# 04_-_7_SEGMENT_DISPS.net
KiCad netlist of a schematic drawn in Altium Designer
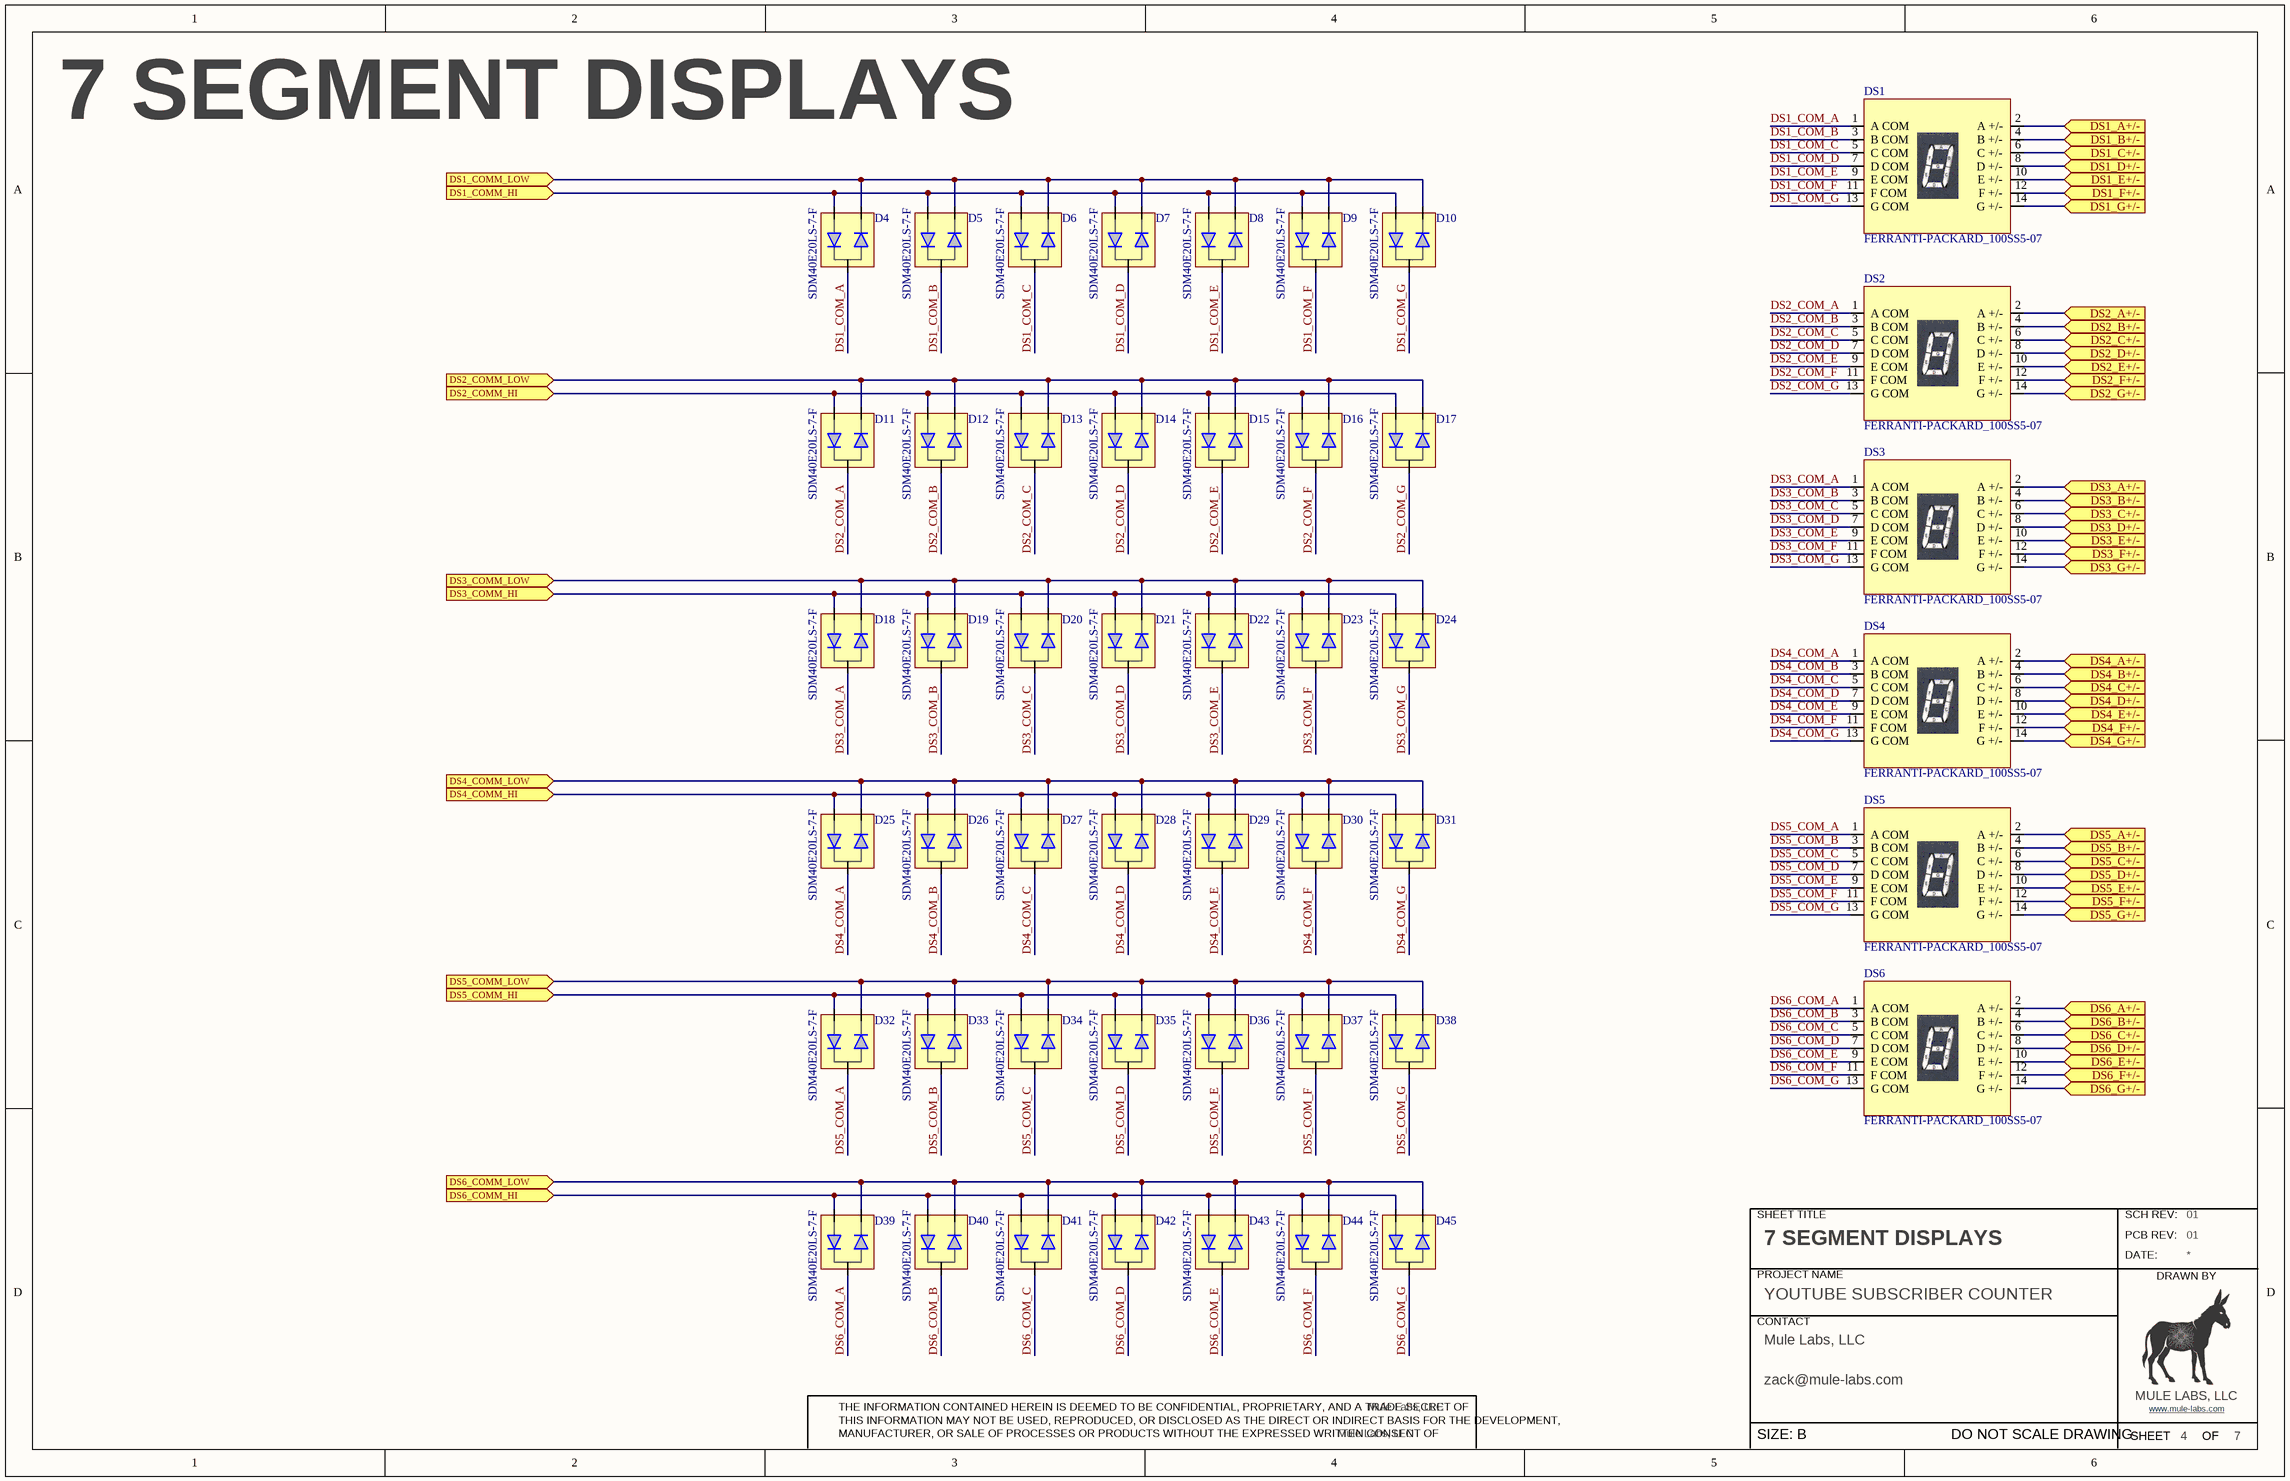
[diagram p0: [04] - 7 SEGMENT DISPS.SchDoc]

(export (version "E")
  (design (tool "Eeschema 10.0.6"))
  (components
    (comp (ref "D4")
      (value "SDM40E20LS-7-F")
      (footprint "SOT23-3P95_240X110L40X44")
      (description "DIODE ARRAY SCHOTTKY 20V SOT23-3")
      (fields (field (name "MANUFACTURER") "Diodes"))
      (libsource (lib "Diodes") (part "SDM40E20LS-7-F"))
    )
    (comp (ref "D5")
      (value "SDM40E20LS-7-F")
      (footprint "SOT23-3P95_240X110L40X44")
      (description "DIODE ARRAY SCHOTTKY 20V SOT23-3")
      (fields (field (name "MANUFACTURER") "Diodes"))
      (libsource (lib "Diodes") (part "SDM40E20LS-7-F"))
    )
    (comp (ref "D6")
      (value "SDM40E20LS-7-F")
      (footprint "SOT23-3P95_240X110L40X44")
      (description "DIODE ARRAY SCHOTTKY 20V SOT23-3")
      (fields (field (name "MANUFACTURER") "Diodes"))
      (libsource (lib "Diodes") (part "SDM40E20LS-7-F"))
    )
    (comp (ref "D7")
      (value "SDM40E20LS-7-F")
      (footprint "SOT23-3P95_240X110L40X44")
      (description "DIODE ARRAY SCHOTTKY 20V SOT23-3")
      (fields (field (name "MANUFACTURER") "Diodes"))
      (libsource (lib "Diodes") (part "SDM40E20LS-7-F"))
    )
    (comp (ref "D8")
      (value "SDM40E20LS-7-F")
      (footprint "SOT23-3P95_240X110L40X44")
      (description "DIODE ARRAY SCHOTTKY 20V SOT23-3")
      (fields (field (name "MANUFACTURER") "Diodes"))
      (libsource (lib "Diodes") (part "SDM40E20LS-7-F"))
    )
    (comp (ref "D9")
      (value "SDM40E20LS-7-F")
      (footprint "SOT23-3P95_240X110L40X44")
      (description "DIODE ARRAY SCHOTTKY 20V SOT23-3")
      (fields (field (name "MANUFACTURER") "Diodes"))
      (libsource (lib "Diodes") (part "SDM40E20LS-7-F"))
    )
    (comp (ref "D10")
      (value "SDM40E20LS-7-F")
      (footprint "SOT23-3P95_240X110L40X44")
      (description "DIODE ARRAY SCHOTTKY 20V SOT23-3")
      (fields (field (name "MANUFACTURER") "Diodes"))
      (libsource (lib "Diodes") (part "SDM40E20LS-7-F"))
    )
    (comp (ref "D11")
      (value "SDM40E20LS-7-F")
      (footprint "SOT23-3P95_240X110L40X44")
      (description "DIODE ARRAY SCHOTTKY 20V SOT23-3")
      (fields (field (name "MANUFACTURER") "Diodes"))
      (libsource (lib "Diodes") (part "SDM40E20LS-7-F"))
    )
    (comp (ref "D12")
      (value "SDM40E20LS-7-F")
      (footprint "SOT23-3P95_240X110L40X44")
      (description "DIODE ARRAY SCHOTTKY 20V SOT23-3")
      (fields (field (name "MANUFACTURER") "Diodes"))
      (libsource (lib "Diodes") (part "SDM40E20LS-7-F"))
    )
    (comp (ref "D13")
      (value "SDM40E20LS-7-F")
      (footprint "SOT23-3P95_240X110L40X44")
      (description "DIODE ARRAY SCHOTTKY 20V SOT23-3")
      (fields (field (name "MANUFACTURER") "Diodes"))
      (libsource (lib "Diodes") (part "SDM40E20LS-7-F"))
    )
    (comp (ref "D14")
      (value "SDM40E20LS-7-F")
      (footprint "SOT23-3P95_240X110L40X44")
      (description "DIODE ARRAY SCHOTTKY 20V SOT23-3")
      (fields (field (name "MANUFACTURER") "Diodes"))
      (libsource (lib "Diodes") (part "SDM40E20LS-7-F"))
    )
    (comp (ref "D15")
      (value "SDM40E20LS-7-F")
      (footprint "SOT23-3P95_240X110L40X44")
      (description "DIODE ARRAY SCHOTTKY 20V SOT23-3")
      (fields (field (name "MANUFACTURER") "Diodes"))
      (libsource (lib "Diodes") (part "SDM40E20LS-7-F"))
    )
    (comp (ref "D16")
      (value "SDM40E20LS-7-F")
      (footprint "SOT23-3P95_240X110L40X44")
      (description "DIODE ARRAY SCHOTTKY 20V SOT23-3")
      (fields (field (name "MANUFACTURER") "Diodes"))
      (libsource (lib "Diodes") (part "SDM40E20LS-7-F"))
    )
    (comp (ref "D17")
      (value "SDM40E20LS-7-F")
      (footprint "SOT23-3P95_240X110L40X44")
      (description "DIODE ARRAY SCHOTTKY 20V SOT23-3")
      (fields (field (name "MANUFACTURER") "Diodes"))
      (libsource (lib "Diodes") (part "SDM40E20LS-7-F"))
    )
    (comp (ref "D18")
      (value "SDM40E20LS-7-F")
      (footprint "SOT23-3P95_240X110L40X44")
      (description "DIODE ARRAY SCHOTTKY 20V SOT23-3")
      (fields (field (name "MANUFACTURER") "Diodes"))
      (libsource (lib "Diodes") (part "SDM40E20LS-7-F"))
    )
    (comp (ref "D19")
      (value "SDM40E20LS-7-F")
      (footprint "SOT23-3P95_240X110L40X44")
      (description "DIODE ARRAY SCHOTTKY 20V SOT23-3")
      (fields (field (name "MANUFACTURER") "Diodes"))
      (libsource (lib "Diodes") (part "SDM40E20LS-7-F"))
    )
    (comp (ref "D20")
      (value "SDM40E20LS-7-F")
      (footprint "SOT23-3P95_240X110L40X44")
      (description "DIODE ARRAY SCHOTTKY 20V SOT23-3")
      (fields (field (name "MANUFACTURER") "Diodes"))
      (libsource (lib "Diodes") (part "SDM40E20LS-7-F"))
    )
    (comp (ref "D21")
      (value "SDM40E20LS-7-F")
      (footprint "SOT23-3P95_240X110L40X44")
      (description "DIODE ARRAY SCHOTTKY 20V SOT23-3")
      (fields (field (name "MANUFACTURER") "Diodes"))
      (libsource (lib "Diodes") (part "SDM40E20LS-7-F"))
    )
    (comp (ref "D22")
      (value "SDM40E20LS-7-F")
      (footprint "SOT23-3P95_240X110L40X44")
      (description "DIODE ARRAY SCHOTTKY 20V SOT23-3")
      (fields (field (name "MANUFACTURER") "Diodes"))
      (libsource (lib "Diodes") (part "SDM40E20LS-7-F"))
    )
    (comp (ref "D23")
      (value "SDM40E20LS-7-F")
      (footprint "SOT23-3P95_240X110L40X44")
      (description "DIODE ARRAY SCHOTTKY 20V SOT23-3")
      (fields (field (name "MANUFACTURER") "Diodes"))
      (libsource (lib "Diodes") (part "SDM40E20LS-7-F"))
    )
    (comp (ref "D24")
      (value "SDM40E20LS-7-F")
      (footprint "SOT23-3P95_240X110L40X44")
      (description "DIODE ARRAY SCHOTTKY 20V SOT23-3")
      (fields (field (name "MANUFACTURER") "Diodes"))
      (libsource (lib "Diodes") (part "SDM40E20LS-7-F"))
    )
    (comp (ref "D25")
      (value "SDM40E20LS-7-F")
      (footprint "SOT23-3P95_240X110L40X44")
      (description "DIODE ARRAY SCHOTTKY 20V SOT23-3")
      (fields (field (name "MANUFACTURER") "Diodes"))
      (libsource (lib "Diodes") (part "SDM40E20LS-7-F"))
    )
    (comp (ref "D26")
      (value "SDM40E20LS-7-F")
      (footprint "SOT23-3P95_240X110L40X44")
      (description "DIODE ARRAY SCHOTTKY 20V SOT23-3")
      (fields (field (name "MANUFACTURER") "Diodes"))
      (libsource (lib "Diodes") (part "SDM40E20LS-7-F"))
    )
    (comp (ref "D27")
      (value "SDM40E20LS-7-F")
      (footprint "SOT23-3P95_240X110L40X44")
      (description "DIODE ARRAY SCHOTTKY 20V SOT23-3")
      (fields (field (name "MANUFACTURER") "Diodes"))
      (libsource (lib "Diodes") (part "SDM40E20LS-7-F"))
    )
    (comp (ref "D28")
      (value "SDM40E20LS-7-F")
      (footprint "SOT23-3P95_240X110L40X44")
      (description "DIODE ARRAY SCHOTTKY 20V SOT23-3")
      (fields (field (name "MANUFACTURER") "Diodes"))
      (libsource (lib "Diodes") (part "SDM40E20LS-7-F"))
    )
    (comp (ref "D29")
      (value "SDM40E20LS-7-F")
      (footprint "SOT23-3P95_240X110L40X44")
      (description "DIODE ARRAY SCHOTTKY 20V SOT23-3")
      (fields (field (name "MANUFACTURER") "Diodes"))
      (libsource (lib "Diodes") (part "SDM40E20LS-7-F"))
    )
    (comp (ref "D30")
      (value "SDM40E20LS-7-F")
      (footprint "SOT23-3P95_240X110L40X44")
      (description "DIODE ARRAY SCHOTTKY 20V SOT23-3")
      (fields (field (name "MANUFACTURER") "Diodes"))
      (libsource (lib "Diodes") (part "SDM40E20LS-7-F"))
    )
    (comp (ref "D31")
      (value "SDM40E20LS-7-F")
      (footprint "SOT23-3P95_240X110L40X44")
      (description "DIODE ARRAY SCHOTTKY 20V SOT23-3")
      (fields (field (name "MANUFACTURER") "Diodes"))
      (libsource (lib "Diodes") (part "SDM40E20LS-7-F"))
    )
    (comp (ref "D32")
      (value "SDM40E20LS-7-F")
      (footprint "SOT23-3P95_240X110L40X44")
      (description "DIODE ARRAY SCHOTTKY 20V SOT23-3")
      (fields (field (name "MANUFACTURER") "Diodes"))
      (libsource (lib "Diodes") (part "SDM40E20LS-7-F"))
    )
    (comp (ref "D33")
      (value "SDM40E20LS-7-F")
      (footprint "SOT23-3P95_240X110L40X44")
      (description "DIODE ARRAY SCHOTTKY 20V SOT23-3")
      (fields (field (name "MANUFACTURER") "Diodes"))
      (libsource (lib "Diodes") (part "SDM40E20LS-7-F"))
    )
    (comp (ref "D34")
      (value "SDM40E20LS-7-F")
      (footprint "SOT23-3P95_240X110L40X44")
      (description "DIODE ARRAY SCHOTTKY 20V SOT23-3")
      (fields (field (name "MANUFACTURER") "Diodes"))
      (libsource (lib "Diodes") (part "SDM40E20LS-7-F"))
    )
    (comp (ref "D35")
      (value "SDM40E20LS-7-F")
      (footprint "SOT23-3P95_240X110L40X44")
      (description "DIODE ARRAY SCHOTTKY 20V SOT23-3")
      (fields (field (name "MANUFACTURER") "Diodes"))
      (libsource (lib "Diodes") (part "SDM40E20LS-7-F"))
    )
    (comp (ref "D36")
      (value "SDM40E20LS-7-F")
      (footprint "SOT23-3P95_240X110L40X44")
      (description "DIODE ARRAY SCHOTTKY 20V SOT23-3")
      (fields (field (name "MANUFACTURER") "Diodes"))
      (libsource (lib "Diodes") (part "SDM40E20LS-7-F"))
    )
    (comp (ref "D37")
      (value "SDM40E20LS-7-F")
      (footprint "SOT23-3P95_240X110L40X44")
      (description "DIODE ARRAY SCHOTTKY 20V SOT23-3")
      (fields (field (name "MANUFACTURER") "Diodes"))
      (libsource (lib "Diodes") (part "SDM40E20LS-7-F"))
    )
    (comp (ref "D38")
      (value "SDM40E20LS-7-F")
      (footprint "SOT23-3P95_240X110L40X44")
      (description "DIODE ARRAY SCHOTTKY 20V SOT23-3")
      (fields (field (name "MANUFACTURER") "Diodes"))
      (libsource (lib "Diodes") (part "SDM40E20LS-7-F"))
    )
    (comp (ref "D39")
      (value "SDM40E20LS-7-F")
      (footprint "SOT23-3P95_240X110L40X44")
      (description "DIODE ARRAY SCHOTTKY 20V SOT23-3")
      (fields (field (name "MANUFACTURER") "Diodes"))
      (libsource (lib "Diodes") (part "SDM40E20LS-7-F"))
    )
    (comp (ref "D40")
      (value "SDM40E20LS-7-F")
      (footprint "SOT23-3P95_240X110L40X44")
      (description "DIODE ARRAY SCHOTTKY 20V SOT23-3")
      (fields (field (name "MANUFACTURER") "Diodes"))
      (libsource (lib "Diodes") (part "SDM40E20LS-7-F"))
    )
    (comp (ref "D41")
      (value "SDM40E20LS-7-F")
      (footprint "SOT23-3P95_240X110L40X44")
      (description "DIODE ARRAY SCHOTTKY 20V SOT23-3")
      (fields (field (name "MANUFACTURER") "Diodes"))
      (libsource (lib "Diodes") (part "SDM40E20LS-7-F"))
    )
    (comp (ref "D42")
      (value "SDM40E20LS-7-F")
      (footprint "SOT23-3P95_240X110L40X44")
      (description "DIODE ARRAY SCHOTTKY 20V SOT23-3")
      (fields (field (name "MANUFACTURER") "Diodes"))
      (libsource (lib "Diodes") (part "SDM40E20LS-7-F"))
    )
    (comp (ref "D43")
      (value "SDM40E20LS-7-F")
      (footprint "SOT23-3P95_240X110L40X44")
      (description "DIODE ARRAY SCHOTTKY 20V SOT23-3")
      (fields (field (name "MANUFACTURER") "Diodes"))
      (libsource (lib "Diodes") (part "SDM40E20LS-7-F"))
    )
    (comp (ref "D44")
      (value "SDM40E20LS-7-F")
      (footprint "SOT23-3P95_240X110L40X44")
      (description "DIODE ARRAY SCHOTTKY 20V SOT23-3")
      (fields (field (name "MANUFACTURER") "Diodes"))
      (libsource (lib "Diodes") (part "SDM40E20LS-7-F"))
    )
    (comp (ref "D45")
      (value "SDM40E20LS-7-F")
      (footprint "SOT23-3P95_240X110L40X44")
      (description "DIODE ARRAY SCHOTTKY 20V SOT23-3")
      (fields (field (name "MANUFACTURER") "Diodes"))
      (libsource (lib "Diodes") (part "SDM40E20LS-7-F"))
    )
    (comp (ref "DS1")
      (value "FERRANTI-PACKARD_100SS5-07")
      (footprint "FERRANTI_EM_7SEG")
      (description "ELECTROMECHANICAL 7-SEGMENT DISPLAY")
      (libsource (lib "Displays") (part "FERRANTI_PACKARD_7SEG"))
    )
    (comp (ref "DS2")
      (value "FERRANTI-PACKARD_100SS5-07")
      (footprint "FERRANTI_EM_7SEG")
      (description "ELECTROMECHANICAL 7-SEGMENT DISPLAY")
      (libsource (lib "Displays") (part "FERRANTI_PACKARD_7SEG"))
    )
    (comp (ref "DS3")
      (value "FERRANTI-PACKARD_100SS5-07")
      (footprint "FERRANTI_EM_7SEG")
      (description "ELECTROMECHANICAL 7-SEGMENT DISPLAY")
      (libsource (lib "Displays") (part "FERRANTI_PACKARD_7SEG"))
    )
    (comp (ref "DS4")
      (value "FERRANTI-PACKARD_100SS5-07")
      (footprint "FERRANTI_EM_7SEG")
      (description "ELECTROMECHANICAL 7-SEGMENT DISPLAY")
      (libsource (lib "Displays") (part "FERRANTI_PACKARD_7SEG"))
    )
    (comp (ref "DS5")
      (value "FERRANTI-PACKARD_100SS5-07")
      (footprint "FERRANTI_EM_7SEG")
      (description "ELECTROMECHANICAL 7-SEGMENT DISPLAY")
      (libsource (lib "Displays") (part "FERRANTI_PACKARD_7SEG"))
    )
    (comp (ref "DS6")
      (value "FERRANTI-PACKARD_100SS5-07")
      (footprint "FERRANTI_EM_7SEG")
      (description "ELECTROMECHANICAL 7-SEGMENT DISPLAY")
      (libsource (lib "Displays") (part "FERRANTI_PACKARD_7SEG"))
    )
  )
  (nets
    (net (code "1") (name "/DS1_A+{slash}-") (class "Default")
      (node (ref "DS1") (pin "2") (pinfunction "A_+/-_2") (pintype "passive"))
    )
    (net (code "2") (name "/DS1_B+{slash}-") (class "Default")
      (node (ref "DS1") (pin "4") (pinfunction "B_+/-_4") (pintype "passive"))
    )
    (net (code "3") (name "/DS1_C+{slash}-") (class "Default")
      (node (ref "DS1") (pin "6") (pinfunction "C_+/-_6") (pintype "passive"))
    )
    (net (code "4") (name "/DS1_COMM_HI") (class "Default")
      (node (ref "D10") (pin "1") (pintype "passive"))
      (node (ref "D4") (pin "1") (pintype "passive"))
      (node (ref "D5") (pin "1") (pintype "passive"))
      (node (ref "D6") (pin "1") (pintype "passive"))
      (node (ref "D7") (pin "1") (pintype "passive"))
      (node (ref "D8") (pin "1") (pintype "passive"))
      (node (ref "D9") (pin "1") (pintype "passive"))
    )
    (net (code "5") (name "/DS1_COMM_LOW") (class "Default")
      (node (ref "D10") (pin "2") (pintype "passive"))
      (node (ref "D4") (pin "2") (pintype "passive"))
      (node (ref "D5") (pin "2") (pintype "passive"))
      (node (ref "D6") (pin "2") (pintype "passive"))
      (node (ref "D7") (pin "2") (pintype "passive"))
      (node (ref "D8") (pin "2") (pintype "passive"))
      (node (ref "D9") (pin "2") (pintype "passive"))
    )
    (net (code "6") (name "/DS1_COM_A") (class "Default")
      (node (ref "D4") (pin "3") (pintype "passive"))
      (node (ref "DS1") (pin "1") (pinfunction "A_COM_1") (pintype "passive"))
    )
    (net (code "7") (name "/DS1_COM_B") (class "Default")
      (node (ref "D5") (pin "3") (pintype "passive"))
      (node (ref "DS1") (pin "3") (pinfunction "B_COM_3") (pintype "passive"))
    )
    (net (code "8") (name "/DS1_COM_C") (class "Default")
      (node (ref "D6") (pin "3") (pintype "passive"))
      (node (ref "DS1") (pin "5") (pinfunction "C_COM_5") (pintype "passive"))
    )
    (net (code "9") (name "/DS1_COM_D") (class "Default")
      (node (ref "D7") (pin "3") (pintype "passive"))
      (node (ref "DS1") (pin "7") (pinfunction "D_COM_7") (pintype "passive"))
    )
    (net (code "10") (name "/DS1_COM_E") (class "Default")
      (node (ref "D8") (pin "3") (pintype "passive"))
      (node (ref "DS1") (pin "9") (pinfunction "E_COM_9") (pintype "passive"))
    )
    (net (code "11") (name "/DS1_COM_F") (class "Default")
      (node (ref "D9") (pin "3") (pintype "passive"))
      (node (ref "DS1") (pin "11") (pinfunction "F_COM_11") (pintype "passive"))
    )
    (net (code "12") (name "/DS1_COM_G") (class "Default")
      (node (ref "D10") (pin "3") (pintype "passive"))
      (node (ref "DS1") (pin "13") (pinfunction "G_COM_13") (pintype "passive"))
    )
    (net (code "13") (name "/DS1_D+{slash}-") (class "Default")
      (node (ref "DS1") (pin "8") (pinfunction "D_+/-_8") (pintype "passive"))
    )
    (net (code "14") (name "/DS1_E+{slash}-") (class "Default")
      (node (ref "DS1") (pin "10") (pinfunction "E_+/-_10") (pintype "passive"))
    )
    (net (code "15") (name "/DS1_F+{slash}-") (class "Default")
      (node (ref "DS1") (pin "12") (pinfunction "F_+/-_12") (pintype "passive"))
    )
    (net (code "16") (name "/DS1_G+{slash}-") (class "Default")
      (node (ref "DS1") (pin "14") (pinfunction "G_+/-_14") (pintype "passive"))
    )
    (net (code "17") (name "/DS2_A+{slash}-") (class "Default")
      (node (ref "DS2") (pin "2") (pinfunction "A_+/-_2") (pintype "passive"))
    )
    (net (code "18") (name "/DS2_B+{slash}-") (class "Default")
      (node (ref "DS2") (pin "4") (pinfunction "B_+/-_4") (pintype "passive"))
    )
    (net (code "19") (name "/DS2_C+{slash}-") (class "Default")
      (node (ref "DS2") (pin "6") (pinfunction "C_+/-_6") (pintype "passive"))
    )
    (net (code "20") (name "/DS2_COMM_HI") (class "Default")
      (node (ref "D11") (pin "1") (pintype "passive"))
      (node (ref "D12") (pin "1") (pintype "passive"))
      (node (ref "D13") (pin "1") (pintype "passive"))
      (node (ref "D14") (pin "1") (pintype "passive"))
      (node (ref "D15") (pin "1") (pintype "passive"))
      (node (ref "D16") (pin "1") (pintype "passive"))
      (node (ref "D17") (pin "1") (pintype "passive"))
    )
    (net (code "21") (name "/DS2_COMM_LOW") (class "Default")
      (node (ref "D11") (pin "2") (pintype "passive"))
      (node (ref "D12") (pin "2") (pintype "passive"))
      (node (ref "D13") (pin "2") (pintype "passive"))
      (node (ref "D14") (pin "2") (pintype "passive"))
      (node (ref "D15") (pin "2") (pintype "passive"))
      (node (ref "D16") (pin "2") (pintype "passive"))
      (node (ref "D17") (pin "2") (pintype "passive"))
    )
    (net (code "22") (name "/DS2_COM_A") (class "Default")
      (node (ref "D11") (pin "3") (pintype "passive"))
      (node (ref "DS2") (pin "1") (pinfunction "A_COM_1") (pintype "passive"))
    )
    (net (code "23") (name "/DS2_COM_B") (class "Default")
      (node (ref "D12") (pin "3") (pintype "passive"))
      (node (ref "DS2") (pin "3") (pinfunction "B_COM_3") (pintype "passive"))
    )
    (net (code "24") (name "/DS2_COM_C") (class "Default")
      (node (ref "D13") (pin "3") (pintype "passive"))
      (node (ref "DS2") (pin "5") (pinfunction "C_COM_5") (pintype "passive"))
    )
    (net (code "25") (name "/DS2_COM_D") (class "Default")
      (node (ref "D14") (pin "3") (pintype "passive"))
      (node (ref "DS2") (pin "7") (pinfunction "D_COM_7") (pintype "passive"))
    )
    (net (code "26") (name "/DS2_COM_E") (class "Default")
      (node (ref "D15") (pin "3") (pintype "passive"))
      (node (ref "DS2") (pin "9") (pinfunction "E_COM_9") (pintype "passive"))
    )
    (net (code "27") (name "/DS2_COM_F") (class "Default")
      (node (ref "D16") (pin "3") (pintype "passive"))
      (node (ref "DS2") (pin "11") (pinfunction "F_COM_11") (pintype "passive"))
    )
    (net (code "28") (name "/DS2_COM_G") (class "Default")
      (node (ref "D17") (pin "3") (pintype "passive"))
      (node (ref "DS2") (pin "13") (pinfunction "G_COM_13") (pintype "passive"))
    )
    (net (code "29") (name "/DS2_D+{slash}-") (class "Default")
      (node (ref "DS2") (pin "8") (pinfunction "D_+/-_8") (pintype "passive"))
    )
    (net (code "30") (name "/DS2_E+{slash}-") (class "Default")
      (node (ref "DS2") (pin "10") (pinfunction "E_+/-_10") (pintype "passive"))
    )
    (net (code "31") (name "/DS2_F+{slash}-") (class "Default")
      (node (ref "DS2") (pin "12") (pinfunction "F_+/-_12") (pintype "passive"))
    )
    (net (code "32") (name "/DS2_G+{slash}-") (class "Default")
      (node (ref "DS2") (pin "14") (pinfunction "G_+/-_14") (pintype "passive"))
    )
    (net (code "33") (name "/DS3_A+{slash}-") (class "Default")
      (node (ref "DS3") (pin "2") (pinfunction "A_+/-_2") (pintype "passive"))
    )
    (net (code "34") (name "/DS3_B+{slash}-") (class "Default")
      (node (ref "DS3") (pin "4") (pinfunction "B_+/-_4") (pintype "passive"))
    )
    (net (code "35") (name "/DS3_C+{slash}-") (class "Default")
      (node (ref "DS3") (pin "6") (pinfunction "C_+/-_6") (pintype "passive"))
    )
    (net (code "36") (name "/DS3_COMM_HI") (class "Default")
      (node (ref "D18") (pin "1") (pintype "passive"))
      (node (ref "D19") (pin "1") (pintype "passive"))
      (node (ref "D20") (pin "1") (pintype "passive"))
      (node (ref "D21") (pin "1") (pintype "passive"))
      (node (ref "D22") (pin "1") (pintype "passive"))
      (node (ref "D23") (pin "1") (pintype "passive"))
      (node (ref "D24") (pin "1") (pintype "passive"))
    )
    (net (code "37") (name "/DS3_COMM_LOW") (class "Default")
      (node (ref "D18") (pin "2") (pintype "passive"))
      (node (ref "D19") (pin "2") (pintype "passive"))
      (node (ref "D20") (pin "2") (pintype "passive"))
      (node (ref "D21") (pin "2") (pintype "passive"))
      (node (ref "D22") (pin "2") (pintype "passive"))
      (node (ref "D23") (pin "2") (pintype "passive"))
      (node (ref "D24") (pin "2") (pintype "passive"))
    )
    (net (code "38") (name "/DS3_COM_A") (class "Default")
      (node (ref "D18") (pin "3") (pintype "passive"))
      (node (ref "DS3") (pin "1") (pinfunction "A_COM_1") (pintype "passive"))
    )
    (net (code "39") (name "/DS3_COM_B") (class "Default")
      (node (ref "D19") (pin "3") (pintype "passive"))
      (node (ref "DS3") (pin "3") (pinfunction "B_COM_3") (pintype "passive"))
    )
    (net (code "40") (name "/DS3_COM_C") (class "Default")
      (node (ref "D20") (pin "3") (pintype "passive"))
      (node (ref "DS3") (pin "5") (pinfunction "C_COM_5") (pintype "passive"))
    )
    (net (code "41") (name "/DS3_COM_D") (class "Default")
      (node (ref "D21") (pin "3") (pintype "passive"))
      (node (ref "DS3") (pin "7") (pinfunction "D_COM_7") (pintype "passive"))
    )
    (net (code "42") (name "/DS3_COM_E") (class "Default")
      (node (ref "D22") (pin "3") (pintype "passive"))
      (node (ref "DS3") (pin "9") (pinfunction "E_COM_9") (pintype "passive"))
    )
    (net (code "43") (name "/DS3_COM_F") (class "Default")
      (node (ref "D23") (pin "3") (pintype "passive"))
      (node (ref "DS3") (pin "11") (pinfunction "F_COM_11") (pintype "passive"))
    )
    (net (code "44") (name "/DS3_COM_G") (class "Default")
      (node (ref "D24") (pin "3") (pintype "passive"))
      (node (ref "DS3") (pin "13") (pinfunction "G_COM_13") (pintype "passive"))
    )
    (net (code "45") (name "/DS3_D+{slash}-") (class "Default")
      (node (ref "DS3") (pin "8") (pinfunction "D_+/-_8") (pintype "passive"))
    )
    (net (code "46") (name "/DS3_E+{slash}-") (class "Default")
      (node (ref "DS3") (pin "10") (pinfunction "E_+/-_10") (pintype "passive"))
    )
    (net (code "47") (name "/DS3_F+{slash}-") (class "Default")
      (node (ref "DS3") (pin "12") (pinfunction "F_+/-_12") (pintype "passive"))
    )
    (net (code "48") (name "/DS3_G+{slash}-") (class "Default")
      (node (ref "DS3") (pin "14") (pinfunction "G_+/-_14") (pintype "passive"))
    )
    (net (code "49") (name "/DS4_A+{slash}-") (class "Default")
      (node (ref "DS4") (pin "2") (pinfunction "A_+/-_2") (pintype "passive"))
    )
    (net (code "50") (name "/DS4_B+{slash}-") (class "Default")
      (node (ref "DS4") (pin "4") (pinfunction "B_+/-_4") (pintype "passive"))
    )
    (net (code "51") (name "/DS4_C+{slash}-") (class "Default")
      (node (ref "DS4") (pin "6") (pinfunction "C_+/-_6") (pintype "passive"))
    )
    (net (code "52") (name "/DS4_COMM_HI") (class "Default")
      (node (ref "D25") (pin "1") (pintype "passive"))
      (node (ref "D26") (pin "1") (pintype "passive"))
      (node (ref "D27") (pin "1") (pintype "passive"))
      (node (ref "D28") (pin "1") (pintype "passive"))
      (node (ref "D29") (pin "1") (pintype "passive"))
      (node (ref "D30") (pin "1") (pintype "passive"))
      (node (ref "D31") (pin "1") (pintype "passive"))
    )
    (net (code "53") (name "/DS4_COMM_LOW") (class "Default")
      (node (ref "D25") (pin "2") (pintype "passive"))
      (node (ref "D26") (pin "2") (pintype "passive"))
      (node (ref "D27") (pin "2") (pintype "passive"))
      (node (ref "D28") (pin "2") (pintype "passive"))
      (node (ref "D29") (pin "2") (pintype "passive"))
      (node (ref "D30") (pin "2") (pintype "passive"))
      (node (ref "D31") (pin "2") (pintype "passive"))
    )
    (net (code "54") (name "/DS4_COM_A") (class "Default")
      (node (ref "D25") (pin "3") (pintype "passive"))
      (node (ref "DS4") (pin "1") (pinfunction "A_COM_1") (pintype "passive"))
    )
    (net (code "55") (name "/DS4_COM_B") (class "Default")
      (node (ref "D26") (pin "3") (pintype "passive"))
      (node (ref "DS4") (pin "3") (pinfunction "B_COM_3") (pintype "passive"))
    )
    (net (code "56") (name "/DS4_COM_C") (class "Default")
      (node (ref "D27") (pin "3") (pintype "passive"))
      (node (ref "DS4") (pin "5") (pinfunction "C_COM_5") (pintype "passive"))
    )
    (net (code "57") (name "/DS4_COM_D") (class "Default")
      (node (ref "D28") (pin "3") (pintype "passive"))
      (node (ref "DS4") (pin "7") (pinfunction "D_COM_7") (pintype "passive"))
    )
    (net (code "58") (name "/DS4_COM_E") (class "Default")
      (node (ref "D29") (pin "3") (pintype "passive"))
      (node (ref "DS4") (pin "9") (pinfunction "E_COM_9") (pintype "passive"))
    )
    (net (code "59") (name "/DS4_COM_F") (class "Default")
      (node (ref "D30") (pin "3") (pintype "passive"))
      (node (ref "DS4") (pin "11") (pinfunction "F_COM_11") (pintype "passive"))
    )
    (net (code "60") (name "/DS4_COM_G") (class "Default")
      (node (ref "D31") (pin "3") (pintype "passive"))
      (node (ref "DS4") (pin "13") (pinfunction "G_COM_13") (pintype "passive"))
    )
    (net (code "61") (name "/DS4_D+{slash}-") (class "Default")
      (node (ref "DS4") (pin "8") (pinfunction "D_+/-_8") (pintype "passive"))
    )
    (net (code "62") (name "/DS4_E+{slash}-") (class "Default")
      (node (ref "DS4") (pin "10") (pinfunction "E_+/-_10") (pintype "passive"))
    )
    (net (code "63") (name "/DS4_F+{slash}-") (class "Default")
      (node (ref "DS4") (pin "12") (pinfunction "F_+/-_12") (pintype "passive"))
    )
    (net (code "64") (name "/DS4_G+{slash}-") (class "Default")
      (node (ref "DS4") (pin "14") (pinfunction "G_+/-_14") (pintype "passive"))
    )
    (net (code "65") (name "/DS5_A+{slash}-") (class "Default")
      (node (ref "DS5") (pin "2") (pinfunction "A_+/-_2") (pintype "passive"))
    )
    (net (code "66") (name "/DS5_B+{slash}-") (class "Default")
      (node (ref "DS5") (pin "4") (pinfunction "B_+/-_4") (pintype "passive"))
    )
    (net (code "67") (name "/DS5_C+{slash}-") (class "Default")
      (node (ref "DS5") (pin "6") (pinfunction "C_+/-_6") (pintype "passive"))
    )
    (net (code "68") (name "/DS5_COMM_HI") (class "Default")
      (node (ref "D32") (pin "1") (pintype "passive"))
      (node (ref "D33") (pin "1") (pintype "passive"))
      (node (ref "D34") (pin "1") (pintype "passive"))
      (node (ref "D35") (pin "1") (pintype "passive"))
      (node (ref "D36") (pin "1") (pintype "passive"))
      (node (ref "D37") (pin "1") (pintype "passive"))
      (node (ref "D38") (pin "1") (pintype "passive"))
    )
    (net (code "69") (name "/DS5_COMM_LOW") (class "Default")
      (node (ref "D32") (pin "2") (pintype "passive"))
      (node (ref "D33") (pin "2") (pintype "passive"))
      (node (ref "D34") (pin "2") (pintype "passive"))
      (node (ref "D35") (pin "2") (pintype "passive"))
      (node (ref "D36") (pin "2") (pintype "passive"))
      (node (ref "D37") (pin "2") (pintype "passive"))
      (node (ref "D38") (pin "2") (pintype "passive"))
    )
    (net (code "70") (name "/DS5_COM_A") (class "Default")
      (node (ref "D32") (pin "3") (pintype "passive"))
      (node (ref "DS5") (pin "1") (pinfunction "A_COM_1") (pintype "passive"))
    )
    (net (code "71") (name "/DS5_COM_B") (class "Default")
      (node (ref "D33") (pin "3") (pintype "passive"))
      (node (ref "DS5") (pin "3") (pinfunction "B_COM_3") (pintype "passive"))
    )
    (net (code "72") (name "/DS5_COM_C") (class "Default")
      (node (ref "D34") (pin "3") (pintype "passive"))
      (node (ref "DS5") (pin "5") (pinfunction "C_COM_5") (pintype "passive"))
    )
    (net (code "73") (name "/DS5_COM_D") (class "Default")
      (node (ref "D35") (pin "3") (pintype "passive"))
      (node (ref "DS5") (pin "7") (pinfunction "D_COM_7") (pintype "passive"))
    )
    (net (code "74") (name "/DS5_COM_E") (class "Default")
      (node (ref "D36") (pin "3") (pintype "passive"))
      (node (ref "DS5") (pin "9") (pinfunction "E_COM_9") (pintype "passive"))
    )
    (net (code "75") (name "/DS5_COM_F") (class "Default")
      (node (ref "D37") (pin "3") (pintype "passive"))
      (node (ref "DS5") (pin "11") (pinfunction "F_COM_11") (pintype "passive"))
    )
    (net (code "76") (name "/DS5_COM_G") (class "Default")
      (node (ref "D38") (pin "3") (pintype "passive"))
      (node (ref "DS5") (pin "13") (pinfunction "G_COM_13") (pintype "passive"))
    )
    (net (code "77") (name "/DS5_D+{slash}-") (class "Default")
      (node (ref "DS5") (pin "8") (pinfunction "D_+/-_8") (pintype "passive"))
    )
    (net (code "78") (name "/DS5_E+{slash}-") (class "Default")
      (node (ref "DS5") (pin "10") (pinfunction "E_+/-_10") (pintype "passive"))
    )
    (net (code "79") (name "/DS5_F+{slash}-") (class "Default")
      (node (ref "DS5") (pin "12") (pinfunction "F_+/-_12") (pintype "passive"))
    )
    (net (code "80") (name "/DS5_G+{slash}-") (class "Default")
      (node (ref "DS5") (pin "14") (pinfunction "G_+/-_14") (pintype "passive"))
    )
    (net (code "81") (name "/DS6_A+{slash}-") (class "Default")
      (node (ref "DS6") (pin "2") (pinfunction "A_+/-_2") (pintype "passive"))
    )
    (net (code "82") (name "/DS6_B+{slash}-") (class "Default")
      (node (ref "DS6") (pin "4") (pinfunction "B_+/-_4") (pintype "passive"))
    )
    (net (code "83") (name "/DS6_C+{slash}-") (class "Default")
      (node (ref "DS6") (pin "6") (pinfunction "C_+/-_6") (pintype "passive"))
    )
    (net (code "84") (name "/DS6_COMM_HI") (class "Default")
      (node (ref "D39") (pin "1") (pintype "passive"))
      (node (ref "D40") (pin "1") (pintype "passive"))
      (node (ref "D41") (pin "1") (pintype "passive"))
      (node (ref "D42") (pin "1") (pintype "passive"))
      (node (ref "D43") (pin "1") (pintype "passive"))
      (node (ref "D44") (pin "1") (pintype "passive"))
      (node (ref "D45") (pin "1") (pintype "passive"))
    )
    (net (code "85") (name "/DS6_COMM_LOW") (class "Default")
      (node (ref "D39") (pin "2") (pintype "passive"))
      (node (ref "D40") (pin "2") (pintype "passive"))
      (node (ref "D41") (pin "2") (pintype "passive"))
      (node (ref "D42") (pin "2") (pintype "passive"))
      (node (ref "D43") (pin "2") (pintype "passive"))
      (node (ref "D44") (pin "2") (pintype "passive"))
      (node (ref "D45") (pin "2") (pintype "passive"))
    )
    (net (code "86") (name "/DS6_COM_A") (class "Default")
      (node (ref "D39") (pin "3") (pintype "passive"))
      (node (ref "DS6") (pin "1") (pinfunction "A_COM_1") (pintype "passive"))
    )
    (net (code "87") (name "/DS6_COM_B") (class "Default")
      (node (ref "D40") (pin "3") (pintype "passive"))
      (node (ref "DS6") (pin "3") (pinfunction "B_COM_3") (pintype "passive"))
    )
    (net (code "88") (name "/DS6_COM_C") (class "Default")
      (node (ref "D41") (pin "3") (pintype "passive"))
      (node (ref "DS6") (pin "5") (pinfunction "C_COM_5") (pintype "passive"))
    )
    (net (code "89") (name "/DS6_COM_D") (class "Default")
      (node (ref "D42") (pin "3") (pintype "passive"))
      (node (ref "DS6") (pin "7") (pinfunction "D_COM_7") (pintype "passive"))
    )
    (net (code "90") (name "/DS6_COM_E") (class "Default")
      (node (ref "D43") (pin "3") (pintype "passive"))
      (node (ref "DS6") (pin "9") (pinfunction "E_COM_9") (pintype "passive"))
    )
    (net (code "91") (name "/DS6_COM_F") (class "Default")
      (node (ref "D44") (pin "3") (pintype "passive"))
      (node (ref "DS6") (pin "11") (pinfunction "F_COM_11") (pintype "passive"))
    )
    (net (code "92") (name "/DS6_COM_G") (class "Default")
      (node (ref "D45") (pin "3") (pintype "passive"))
      (node (ref "DS6") (pin "13") (pinfunction "G_COM_13") (pintype "passive"))
    )
    (net (code "93") (name "/DS6_D+{slash}-") (class "Default")
      (node (ref "DS6") (pin "8") (pinfunction "D_+/-_8") (pintype "passive"))
    )
    (net (code "94") (name "/DS6_E+{slash}-") (class "Default")
      (node (ref "DS6") (pin "10") (pinfunction "E_+/-_10") (pintype "passive"))
    )
    (net (code "95") (name "/DS6_F+{slash}-") (class "Default")
      (node (ref "DS6") (pin "12") (pinfunction "F_+/-_12") (pintype "passive"))
    )
    (net (code "96") (name "/DS6_G+{slash}-") (class "Default")
      (node (ref "DS6") (pin "14") (pinfunction "G_+/-_14") (pintype "passive"))
    )
  )
)
